# 03_GSM_GPRS_GPS.net
KiCad netlist of a schematic drawn in Altium Designer
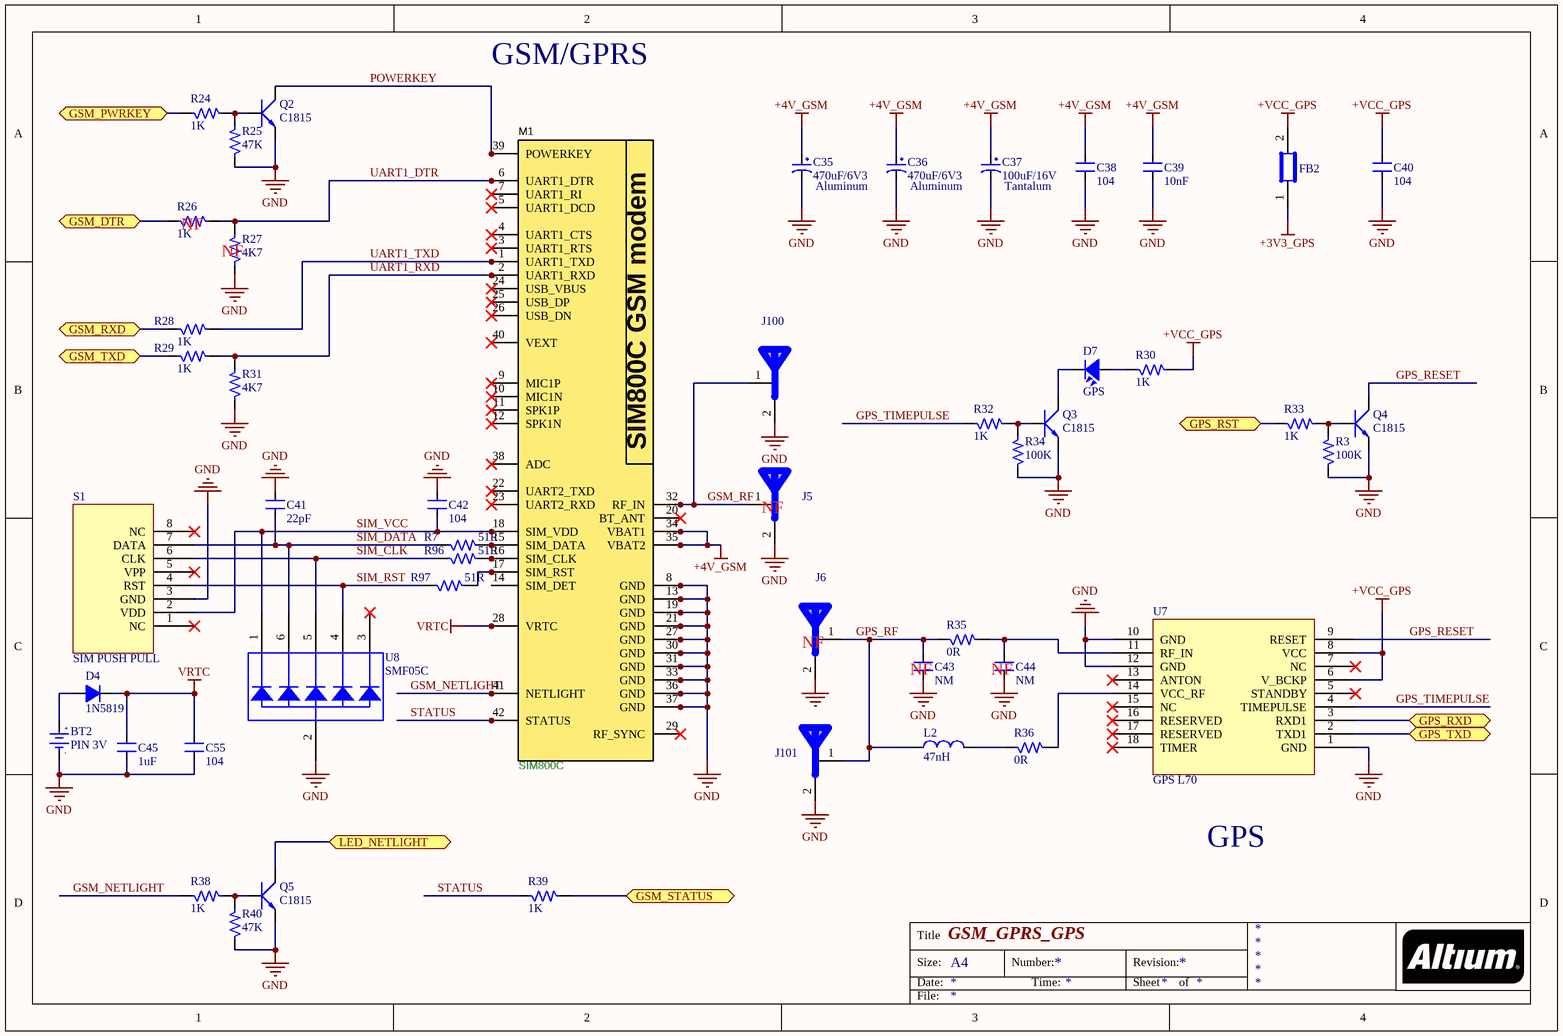
[diagram p0: [03] GSM_GPRS_GPS.SchDoc]

(export (version "E")
  (design (tool "Eeschema 10.0.6"))
  (components
    (comp (ref "BT2")
      (value "PIN 3V")
      (footprint "PIN3V_mini")
      (description "Battery 3VDC")
      (libsource (lib "khapham") (part "PIN 3V"))
    )
    (comp (ref "C35")
      (value "470uF/6V3")
      (footprint "C_Alu_6.3x7.7")
      (description "Cap Aluminum")
      (libsource (lib "khapham") (part "C-Alu-Tantalum"))
    )
    (comp (ref "C36")
      (value "470uF/6V3")
      (footprint "C_Alu_6.3x7.7")
      (description "Cap Aluminum")
      (libsource (lib "khapham") (part "C-Alu-Tantalum"))
    )
    (comp (ref "C37")
      (value "100uF/16V")
      (footprint "C_7343_40")
      (description "Cap Tantalum 7343")
      (libsource (lib "khapham") (part "C-Alu-Tantalum"))
    )
    (comp (ref "C38")
      (value "104")
      (footprint "C0603 SMT")
      (description "Cap SMD")
      (libsource (lib "khapham") (part "CM"))
    )
    (comp (ref "C39")
      (value "10nF")
      (footprint "C0603 SMT")
      (description "Cap SMD")
      (libsource (lib "khapham") (part "CM"))
    )
    (comp (ref "C40")
      (value "104")
      (footprint "C0603 SMT")
      (description "Cap SMD")
      (libsource (lib "khapham") (part "CM"))
    )
    (comp (ref "C41")
      (value "22pF")
      (footprint "C0603 SMT")
      (description "Cap SMD")
      (libsource (lib "khapham") (part "CM"))
    )
    (comp (ref "C42")
      (value "104")
      (footprint "C0603 SMT")
      (description "Cap SMD")
      (libsource (lib "khapham") (part "CM"))
    )
    (comp (ref "C43")
      (value "NM")
      (footprint "C0603 SMT")
      (description "Cap SMD")
      (libsource (lib "khapham") (part "CM"))
    )
    (comp (ref "C44")
      (value "NM")
      (footprint "C0603 SMT")
      (description "Cap SMD")
      (libsource (lib "khapham") (part "CM"))
    )
    (comp (ref "C45")
      (value "1uF")
      (footprint "C0603 SMT")
      (description "Cap SMD")
      (libsource (lib "khapham") (part "CM"))
    )
    (comp (ref "C55")
      (value "104")
      (footprint "C0603 SMT")
      (description "Cap SMD")
      (libsource (lib "khapham") (part "CM"))
    )
    (comp (ref "D4")
      (value "1N5819")
      (footprint "SOD123")
      (description "Diode 1A")
      (libsource (lib "khapham") (part "D1A"))
    )
    (comp (ref "D7")
      (value "GPS")
      (footprint "Led_0603_RED")
      (description "LED Single colour Green and Red")
      (libsource (lib "khapham") (part "LED"))
    )
    (comp (ref "FB2")
      (value "BLM21PG600SN1D")
      (footprint "R0805")
      (description "Ferrite Bead")
      (libsource (lib "khapham") (part "Ferrite Bead"))
    )
    (comp (ref "J5") (value "GSM") (footprint "Antenna-IPEX") (libsource (lib "khapham") (part "ANTEN")))
    (comp (ref "J6") (value "GPS") (footprint "Antenna-IPEX") (libsource (lib "khapham") (part "ANTEN")))
    (comp (ref "J100")
      (value "GPS_ANTENNA")
      (footprint "Antenna-MCX5.08-H5")
      (libsource (lib "khapham") (part "ANTEN"))
    )
    (comp (ref "J101")
      (value "GPS_ANTENNA")
      (footprint "Antenna-MCX5.08-H5")
      (libsource (lib "khapham") (part "ANTEN"))
    )
    (comp (ref "L2")
      (value "47nH")
      (footprint "C0805")
      (description "Inductor")
      (libsource (lib "khapham") (part "L1"))
    )
    (comp (ref "M1") (value "SIM800C") (footprint "SIM800C") (libsource (lib "khapham") (part "SIM800C")))
    (comp (ref "Q2")
      (value "C1815")
      (footprint "SOT23B")
      (description "NPN 600mW, ECB")
      (libsource (lib "khapham") (part "C1815"))
    )
    (comp (ref "Q3")
      (value "C1815")
      (footprint "SOT23B")
      (description "NPN 600mW, ECB")
      (libsource (lib "khapham") (part "C1815"))
    )
    (comp (ref "Q4")
      (value "C1815")
      (footprint "SOT23B")
      (description "NPN 600mW, ECB")
      (libsource (lib "khapham") (part "C1815"))
    )
    (comp (ref "Q5")
      (value "C1815")
      (footprint "SOT23B")
      (description "NPN 600mW, ECB")
      (libsource (lib "khapham") (part "C1815"))
    )
    (comp (ref "R3")
      (value "100K")
      (footprint "R0603 -SMT")
      (description "Resistor SMD")
      (libsource (lib "khapham") (part "RM"))
    )
    (comp (ref "R7")
      (value "51R")
      (footprint "R0603 -SMT")
      (description "Resistor SMD")
      (libsource (lib "khapham") (part "RM"))
    )
    (comp (ref "R24")
      (value "1K")
      (footprint "R0603 -SMT")
      (description "Resistor SMD")
      (libsource (lib "khapham") (part "RM"))
    )
    (comp (ref "R25")
      (value "47K")
      (footprint "R0603 -SMT")
      (description "Resistor SMD")
      (libsource (lib "khapham") (part "RM"))
    )
    (comp (ref "R26")
      (value "1K")
      (footprint "R0603 -SMT")
      (description "Resistor SMD")
      (libsource (lib "khapham") (part "RM"))
    )
    (comp (ref "R27")
      (value "4K7")
      (footprint "R0603 -SMT")
      (description "Resistor SMD")
      (libsource (lib "khapham") (part "RM"))
    )
    (comp (ref "R28")
      (value "1K")
      (footprint "R0603 -SMT")
      (description "Resistor SMD")
      (libsource (lib "khapham") (part "RM"))
    )
    (comp (ref "R29")
      (value "1K")
      (footprint "R0603 -SMT")
      (description "Resistor SMD")
      (libsource (lib "khapham") (part "RM"))
    )
    (comp (ref "R30")
      (value "1K")
      (footprint "R0603 -SMT")
      (description "Resistor SMD")
      (libsource (lib "khapham") (part "RM"))
    )
    (comp (ref "R31")
      (value "4K7")
      (footprint "R0603 -SMT")
      (description "Resistor SMD")
      (libsource (lib "khapham") (part "RM"))
    )
    (comp (ref "R32")
      (value "1K")
      (footprint "R0603 -SMT")
      (description "Resistor SMD")
      (libsource (lib "khapham") (part "RM"))
    )
    (comp (ref "R33")
      (value "1K")
      (footprint "R0603 -SMT")
      (description "Resistor SMD")
      (libsource (lib "khapham") (part "RM"))
    )
    (comp (ref "R34")
      (value "100K")
      (footprint "R0603 -SMT")
      (description "Resistor SMD")
      (libsource (lib "khapham") (part "RM"))
    )
    (comp (ref "R35")
      (value "0R")
      (footprint "R0603 -SMT")
      (description "Resistor SMD")
      (libsource (lib "khapham") (part "RM"))
    )
    (comp (ref "R36")
      (value "0R")
      (footprint "R0603 -SMT")
      (description "Resistor SMD")
      (libsource (lib "khapham") (part "RM"))
    )
    (comp (ref "R38")
      (value "1K")
      (footprint "R0603 -SMT")
      (description "Resistor SMD")
      (libsource (lib "khapham") (part "RM"))
    )
    (comp (ref "R39")
      (value "1K")
      (footprint "R0603 -SMT")
      (description "Resistor SMD")
      (libsource (lib "khapham") (part "RM"))
    )
    (comp (ref "R40")
      (value "47K")
      (footprint "R0603 -SMT")
      (description "Resistor SMD")
      (libsource (lib "khapham") (part "RM"))
    )
    (comp (ref "R96")
      (value "51R")
      (footprint "R0603 -SMT")
      (description "Resistor SMD")
      (libsource (lib "khapham") (part "RM"))
    )
    (comp (ref "R97")
      (value "51R")
      (footprint "R0603 -SMT")
      (description "Resistor SMD")
      (libsource (lib "khapham") (part "RM"))
    )
    (comp (ref "S1")
      (value "SIM PUSH PULL")
      (footprint "Sim Push Push")
      (libsource (lib "khapham") (part "SIM SOCKET PUSH PULL"))
    )
    (comp (ref "U7") (value "GPS L70") (footprint "GPS L70") (libsource (lib "khapham") (part "GPS L70")))
    (comp (ref "U8")
      (value "SMF05C")
      (footprint "SOT_363_6")
      (description "ESD Protection")
      (libsource (lib "khapham") (part "SMF05C"))
    )
  )
  (nets
    (net (code "1") (name "+3V3_GPS") (class "Default")
      (node (ref "FB2") (pin "1") (pinfunction "1_1") (pintype "passive"))
    )
    (net (code "2") (name "+4V_GSM") (class "Default")
      (node (ref "C35") (pin "1") (pinfunction "1_1") (pintype "passive"))
      (node (ref "C36") (pin "1") (pinfunction "1_1") (pintype "passive"))
      (node (ref "C37") (pin "1") (pinfunction "1_1") (pintype "passive"))
      (node (ref "C38") (pin "1") (pinfunction "1_1") (pintype "passive"))
      (node (ref "C39") (pin "1") (pinfunction "1_1") (pintype "passive"))
      (node (ref "M1") (pin "34") (pinfunction "VBAT1_34") (pintype "passive"))
      (node (ref "M1") (pin "35") (pinfunction "VBAT2_35") (pintype "passive"))
    )
    (net (code "3") (name "+VCC_GPS") (class "Default")
      (node (ref "C40") (pin "2") (pinfunction "2_2") (pintype "passive"))
      (node (ref "FB2") (pin "2") (pinfunction "2_2") (pintype "passive"))
      (node (ref "R30") (pin "2") (pinfunction "2_2") (pintype "passive"))
      (node (ref "U7") (pin "6") (pinfunction "V_BCKP_6") (pintype "passive"))
      (node (ref "U7") (pin "8") (pinfunction "VCC_8") (pintype "passive"))
    )
    (net (code "4") (name "/GPS_RESET") (class "Default")
      (node (ref "Q4") (pin "2") (pinfunction "C_2") (pintype "passive"))
      (node (ref "U7") (pin "9") (pinfunction "RESET_9") (pintype "passive"))
    )
    (net (code "5") (name "/GPS_RF") (class "Default")
      (node (ref "C43") (pin "2") (pinfunction "2_2") (pintype "passive"))
      (node (ref "J101") (pin "1") (pinfunction "GND_1") (pintype "passive"))
      (node (ref "J6") (pin "1") (pinfunction "GND_1") (pintype "passive"))
      (node (ref "L2") (pin "1") (pinfunction "1_1") (pintype "passive"))
      (node (ref "R35") (pin "1") (pinfunction "1_1") (pintype "passive"))
    )
    (net (code "6") (name "/GPS_RST") (class "Default")
      (node (ref "R33") (pin "1") (pinfunction "1_1") (pintype "passive"))
    )
    (net (code "7") (name "/GPS_RXD") (class "Default")
      (node (ref "U7") (pin "3") (pinfunction "RXD1_3") (pintype "passive"))
    )
    (net (code "8") (name "/GPS_TIMEPULSE") (class "Default")
      (node (ref "R32") (pin "1") (pinfunction "1_1") (pintype "passive"))
      (node (ref "U7") (pin "4") (pinfunction "TIMEPULSE_4") (pintype "passive"))
    )
    (net (code "9") (name "/GPS_TXD") (class "Default")
      (node (ref "U7") (pin "2") (pinfunction "TXD1_2") (pintype "passive"))
    )
    (net (code "10") (name "/GSM_DTR") (class "Default")
      (node (ref "R26") (pin "1") (pinfunction "1_1") (pintype "passive"))
    )
    (net (code "11") (name "/GSM_NETLIGHT") (class "Default")
      (node (ref "M1") (pin "41") (pinfunction "NETLIGHT_41") (pintype "passive"))
      (node (ref "R38") (pin "1") (pinfunction "1_1") (pintype "passive"))
    )
    (net (code "12") (name "/GSM_PWRKEY") (class "Default")
      (node (ref "R24") (pin "1") (pinfunction "1_1") (pintype "passive"))
    )
    (net (code "13") (name "/GSM_RF") (class "Default")
      (node (ref "J100") (pin "1") (pinfunction "GND_1") (pintype "passive"))
      (node (ref "J5") (pin "1") (pinfunction "GND_1") (pintype "passive"))
      (node (ref "M1") (pin "32") (pinfunction "RF_IN_32") (pintype "passive"))
    )
    (net (code "14") (name "/GSM_RXD") (class "Default")
      (node (ref "R28") (pin "1") (pinfunction "1_1") (pintype "passive"))
    )
    (net (code "15") (name "/GSM_STATUS") (class "Default")
      (node (ref "R39") (pin "2") (pinfunction "2_2") (pintype "passive"))
    )
    (net (code "16") (name "/GSM_TXD") (class "Default")
      (node (ref "R29") (pin "1") (pinfunction "1_1") (pintype "passive"))
    )
    (net (code "17") (name "/LED_NETLIGHT") (class "Default")
      (node (ref "Q5") (pin "2") (pinfunction "C_2") (pintype "passive"))
    )
    (net (code "18") (name "/POWERKEY") (class "Default")
      (node (ref "M1") (pin "39") (pinfunction "POWERKEY_39") (pintype "passive"))
      (node (ref "Q2") (pin "2") (pinfunction "C_2") (pintype "passive"))
    )
    (net (code "19") (name "/SIM_CLK") (class "Default")
      (node (ref "R96") (pin "1") (pinfunction "1_1") (pintype "passive"))
      (node (ref "S1") (pin "6") (pinfunction "CLK_6") (pintype "passive"))
      (node (ref "U8") (pin "5") (pinfunction "K4_5") (pintype "power_in"))
    )
    (net (code "20") (name "/SIM_DATA") (class "Default")
      (node (ref "C41") (pin "1") (pinfunction "1_1") (pintype "passive"))
      (node (ref "R7") (pin "1") (pinfunction "1_1") (pintype "passive"))
      (node (ref "S1") (pin "7") (pinfunction "DATA_7") (pintype "passive"))
      (node (ref "U8") (pin "6") (pinfunction "K5_6") (pintype "passive"))
    )
    (net (code "21") (name "/SIM_RST") (class "Default")
      (node (ref "R97") (pin "1") (pinfunction "1_1") (pintype "passive"))
      (node (ref "S1") (pin "4") (pinfunction "RST_4") (pintype "passive"))
      (node (ref "U8") (pin "4") (pinfunction "K3_4") (pintype "passive"))
    )
    (net (code "22") (name "/SIM_VCC") (class "Default")
      (node (ref "C42") (pin "1") (pinfunction "1_1") (pintype "passive"))
      (node (ref "M1") (pin "18") (pinfunction "SIM_VDD_18") (pintype "passive"))
      (node (ref "S1") (pin "2") (pinfunction "VDD_2") (pintype "passive"))
      (node (ref "U8") (pin "1") (pinfunction "K1_1") (pintype "passive"))
    )
    (net (code "23") (name "/STATUS") (class "Default")
      (node (ref "M1") (pin "42") (pinfunction "STATUS_42") (pintype "passive"))
      (node (ref "R39") (pin "1") (pinfunction "1_1") (pintype "passive"))
    )
    (net (code "24") (name "/UART1_DTR") (class "Default")
      (node (ref "M1") (pin "6") (pinfunction "UART1_DTR_6") (pintype "passive"))
      (node (ref "R26") (pin "2") (pinfunction "2_2") (pintype "passive"))
      (node (ref "R27") (pin "2") (pinfunction "2_2") (pintype "passive"))
    )
    (net (code "25") (name "/UART1_RXD") (class "Default")
      (node (ref "M1") (pin "2") (pinfunction "UART1_RXD_2") (pintype "passive"))
      (node (ref "R29") (pin "2") (pinfunction "2_2") (pintype "passive"))
      (node (ref "R31") (pin "2") (pinfunction "2_2") (pintype "passive"))
    )
    (net (code "26") (name "/UART1_TXD") (class "Default")
      (node (ref "M1") (pin "1") (pinfunction "UART1_TXD_1") (pintype "passive"))
      (node (ref "R28") (pin "2") (pinfunction "2_2") (pintype "passive"))
    )
    (net (code "27") (name "GND") (class "Default")
      (node (ref "BT2") (pin "2") (pinfunction "GND_2") (pintype "passive"))
      (node (ref "C35") (pin "2") (pinfunction "2_2") (pintype "passive"))
      (node (ref "C36") (pin "2") (pinfunction "2_2") (pintype "passive"))
      (node (ref "C37") (pin "2") (pinfunction "2_2") (pintype "passive"))
      (node (ref "C38") (pin "2") (pinfunction "2_2") (pintype "passive"))
      (node (ref "C39") (pin "2") (pinfunction "2_2") (pintype "passive"))
      (node (ref "C40") (pin "1") (pinfunction "1_1") (pintype "passive"))
      (node (ref "C41") (pin "2") (pinfunction "2_2") (pintype "passive"))
      (node (ref "C42") (pin "2") (pinfunction "2_2") (pintype "passive"))
      (node (ref "C43") (pin "1") (pinfunction "1_1") (pintype "passive"))
      (node (ref "C44") (pin "1") (pinfunction "1_1") (pintype "passive"))
      (node (ref "C45") (pin "1") (pinfunction "1_1") (pintype "passive"))
      (node (ref "C55") (pin "1") (pinfunction "1_1") (pintype "passive"))
      (node (ref "J100") (pin "2") (pinfunction "GND_2") (pintype "passive"))
      (node (ref "J101") (pin "2") (pinfunction "GND_2") (pintype "passive"))
      (node (ref "J5") (pin "2") (pinfunction "GND_2") (pintype "passive"))
      (node (ref "J6") (pin "2") (pinfunction "GND_2") (pintype "passive"))
      (node (ref "M1") (pin "13") (pinfunction "GND_13") (pintype "passive"))
      (node (ref "M1") (pin "19") (pinfunction "GND_19") (pintype "passive"))
      (node (ref "M1") (pin "21") (pinfunction "GND_21") (pintype "passive"))
      (node (ref "M1") (pin "27") (pinfunction "GND_27") (pintype "passive"))
      (node (ref "M1") (pin "30") (pinfunction "GND_30") (pintype "passive"))
      (node (ref "M1") (pin "31") (pinfunction "GND_31") (pintype "passive"))
      (node (ref "M1") (pin "33") (pinfunction "GND_33") (pintype "passive"))
      (node (ref "M1") (pin "36") (pinfunction "GND_36") (pintype "passive"))
      (node (ref "M1") (pin "37") (pinfunction "GND_37") (pintype "passive"))
      (node (ref "M1") (pin "8") (pinfunction "GND_8") (pintype "passive"))
      (node (ref "Q2") (pin "1") (pinfunction "E_1") (pintype "passive"))
      (node (ref "Q3") (pin "1") (pinfunction "E_1") (pintype "passive"))
      (node (ref "Q4") (pin "1") (pinfunction "E_1") (pintype "passive"))
      (node (ref "Q5") (pin "1") (pinfunction "E_1") (pintype "passive"))
      (node (ref "R25") (pin "1") (pinfunction "1_1") (pintype "passive"))
      (node (ref "R27") (pin "1") (pinfunction "1_1") (pintype "passive"))
      (node (ref "R3") (pin "1") (pinfunction "1_1") (pintype "passive"))
      (node (ref "R31") (pin "1") (pinfunction "1_1") (pintype "passive"))
      (node (ref "R34") (pin "1") (pinfunction "1_1") (pintype "passive"))
      (node (ref "R40") (pin "1") (pinfunction "1_1") (pintype "passive"))
      (node (ref "S1") (pin "3") (pinfunction "GND_3") (pintype "passive"))
      (node (ref "U7") (pin "1") (pinfunction "GND_1") (pintype "passive"))
      (node (ref "U7") (pin "10") (pinfunction "GND_10") (pintype "passive"))
      (node (ref "U7") (pin "12") (pinfunction "GND_12") (pintype "passive"))
      (node (ref "U8") (pin "2") (pinfunction "A_2") (pintype "power_in"))
    )
    (net (code "28") (name "Net-(BT2-+3V)") (class "Default")
      (node (ref "BT2") (pin "1") (pinfunction "+3V_1") (pintype "passive"))
      (node (ref "D4") (pin "1") (pinfunction "A_1") (pintype "passive"))
    )
    (net (code "29") (name "Net-(D7-Pad1)") (class "Default")
      (node (ref "D7") (pin "1") (pinfunction "1_1") (pintype "passive"))
      (node (ref "R30") (pin "1") (pinfunction "1_1") (pintype "passive"))
    )
    (net (code "30") (name "Net-(L2-Pad2)") (class "Default")
      (node (ref "L2") (pin "2") (pinfunction "2_2") (pintype "passive"))
      (node (ref "R36") (pin "1") (pinfunction "1_1") (pintype "passive"))
    )
    (net (code "31") (name "Net-(M1-SIM_CLK)") (class "Default")
      (node (ref "M1") (pin "16") (pinfunction "SIM_CLK_16") (pintype "passive"))
      (node (ref "R96") (pin "2") (pinfunction "2_2") (pintype "passive"))
    )
    (net (code "32") (name "Net-(M1-SIM_DATA)") (class "Default")
      (node (ref "M1") (pin "15") (pinfunction "SIM_DATA_15") (pintype "passive"))
      (node (ref "R7") (pin "2") (pinfunction "2_2") (pintype "passive"))
    )
    (net (code "33") (name "Net-(M1-SIM_RST)") (class "Default")
      (node (ref "M1") (pin "17") (pinfunction "SIM_RST_17") (pintype "passive"))
      (node (ref "R97") (pin "2") (pinfunction "2_2") (pintype "passive"))
    )
    (net (code "34") (name "Net-(Q2-B)") (class "Default")
      (node (ref "Q2") (pin "3") (pinfunction "B_3") (pintype "passive"))
      (node (ref "R24") (pin "2") (pinfunction "2_2") (pintype "passive"))
      (node (ref "R25") (pin "2") (pinfunction "2_2") (pintype "passive"))
    )
    (net (code "35") (name "Net-(Q3-B)") (class "Default")
      (node (ref "Q3") (pin "3") (pinfunction "B_3") (pintype "passive"))
      (node (ref "R32") (pin "2") (pinfunction "2_2") (pintype "passive"))
      (node (ref "R34") (pin "2") (pinfunction "2_2") (pintype "passive"))
    )
    (net (code "36") (name "Net-(Q3-C)") (class "Default")
      (node (ref "D7") (pin "2") (pinfunction "2_2") (pintype "passive"))
      (node (ref "Q3") (pin "2") (pinfunction "C_2") (pintype "passive"))
    )
    (net (code "37") (name "Net-(Q4-B)") (class "Default")
      (node (ref "Q4") (pin "3") (pinfunction "B_3") (pintype "passive"))
      (node (ref "R3") (pin "2") (pinfunction "2_2") (pintype "passive"))
      (node (ref "R33") (pin "2") (pinfunction "2_2") (pintype "passive"))
    )
    (net (code "38") (name "Net-(Q5-B)") (class "Default")
      (node (ref "Q5") (pin "3") (pinfunction "B_3") (pintype "passive"))
      (node (ref "R38") (pin "2") (pinfunction "2_2") (pintype "passive"))
      (node (ref "R40") (pin "2") (pinfunction "2_2") (pintype "passive"))
    )
    (net (code "39") (name "Net-(U7-RF_IN)") (class "Default")
      (node (ref "C44") (pin "2") (pinfunction "2_2") (pintype "passive"))
      (node (ref "R35") (pin "2") (pinfunction "2_2") (pintype "passive"))
      (node (ref "U7") (pin "11") (pinfunction "RF_IN_11") (pintype "passive"))
    )
    (net (code "40") (name "Net-(U7-VCC_RF)") (class "Default")
      (node (ref "R36") (pin "2") (pinfunction "2_2") (pintype "passive"))
      (node (ref "U7") (pin "14") (pinfunction "VCC_RF_14") (pintype "passive"))
    )
    (net (code "41") (name "VRTC") (class "Default")
      (node (ref "C45") (pin "2") (pinfunction "2_2") (pintype "passive"))
      (node (ref "C55") (pin "2") (pinfunction "2_2") (pintype "passive"))
      (node (ref "D4") (pin "2") (pinfunction "K_2") (pintype "passive"))
      (node (ref "M1") (pin "28") (pinfunction "VRTC_28") (pintype "passive"))
    )
    (net (code "42") (name "unconnected-(M1-ADC-Pad38)") (class "Default")
      (node (ref "M1") (pin "38") (pinfunction "ADC_38") (pintype "passive+no_connect"))
    )
    (net (code "43") (name "unconnected-(M1-BT_ANT-Pad20)") (class "Default")
      (node (ref "M1") (pin "20") (pinfunction "BT_ANT_20") (pintype "passive+no_connect"))
    )
    (net (code "44") (name "unconnected-(M1-MIC1N-Pad10)") (class "Default")
      (node (ref "M1") (pin "10") (pinfunction "MIC1N_10") (pintype "passive+no_connect"))
    )
    (net (code "45") (name "unconnected-(M1-MIC1P-Pad9)") (class "Default")
      (node (ref "M1") (pin "9") (pinfunction "MIC1P_9") (pintype "passive+no_connect"))
    )
    (net (code "46") (name "unconnected-(M1-RF_SYNC-Pad29)") (class "Default")
      (node (ref "M1") (pin "29") (pinfunction "RF_SYNC_29") (pintype "passive+no_connect"))
    )
    (net (code "47") (name "unconnected-(M1-SIM_DET-Pad14)") (class "Default")
      (node (ref "M1") (pin "14") (pinfunction "SIM_DET_14") (pintype "passive"))
    )
    (net (code "48") (name "unconnected-(M1-SPK1N-Pad12)") (class "Default")
      (node (ref "M1") (pin "12") (pinfunction "SPK1N_12") (pintype "passive+no_connect"))
    )
    (net (code "49") (name "unconnected-(M1-SPK1P-Pad11)") (class "Default")
      (node (ref "M1") (pin "11") (pinfunction "SPK1P_11") (pintype "passive+no_connect"))
    )
    (net (code "50") (name "unconnected-(M1-UART1_CTS-Pad4)") (class "Default")
      (node (ref "M1") (pin "4") (pinfunction "UART1_CTS_4") (pintype "passive+no_connect"))
    )
    (net (code "51") (name "unconnected-(M1-UART1_DCD-Pad5)") (class "Default")
      (node (ref "M1") (pin "5") (pinfunction "UART1_DCD_5") (pintype "passive+no_connect"))
    )
    (net (code "52") (name "unconnected-(M1-UART1_RI-Pad7)") (class "Default")
      (node (ref "M1") (pin "7") (pinfunction "UART1_RI_7") (pintype "passive+no_connect"))
    )
    (net (code "53") (name "unconnected-(M1-UART1_RTS-Pad3)") (class "Default")
      (node (ref "M1") (pin "3") (pinfunction "UART1_RTS_3") (pintype "passive+no_connect"))
    )
    (net (code "54") (name "unconnected-(M1-UART2_RXD-Pad23)") (class "Default")
      (node (ref "M1") (pin "23") (pinfunction "UART2_RXD_23") (pintype "passive+no_connect"))
    )
    (net (code "55") (name "unconnected-(M1-UART2_TXD-Pad22)") (class "Default")
      (node (ref "M1") (pin "22") (pinfunction "UART2_TXD_22") (pintype "passive+no_connect"))
    )
    (net (code "56") (name "unconnected-(M1-USB_DN-Pad26)") (class "Default")
      (node (ref "M1") (pin "26") (pinfunction "USB_DN_26") (pintype "passive+no_connect"))
    )
    (net (code "57") (name "unconnected-(M1-USB_DP-Pad25)") (class "Default")
      (node (ref "M1") (pin "25") (pinfunction "USB_DP_25") (pintype "passive+no_connect"))
    )
    (net (code "58") (name "unconnected-(M1-USB_VBUS-Pad24)") (class "Default")
      (node (ref "M1") (pin "24") (pinfunction "USB_VBUS_24") (pintype "passive+no_connect"))
    )
    (net (code "59") (name "unconnected-(M1-VEXT-Pad40)") (class "Default")
      (node (ref "M1") (pin "40") (pinfunction "VEXT_40") (pintype "passive+no_connect"))
    )
    (net (code "60") (name "unconnected-(S1-NC-Pad1)") (class "Default")
      (node (ref "S1") (pin "1") (pinfunction "NC_1") (pintype "passive+no_connect"))
    )
    (net (code "61") (name "unconnected-(S1-NC-Pad8)") (class "Default")
      (node (ref "S1") (pin "8") (pinfunction "NC_8") (pintype "passive+no_connect"))
    )
    (net (code "62") (name "unconnected-(S1-VPP-Pad5)") (class "Default")
      (node (ref "S1") (pin "5") (pinfunction "VPP_5") (pintype "passive+no_connect"))
    )
    (net (code "63") (name "unconnected-(U7-ANTON-Pad13)") (class "Default")
      (node (ref "U7") (pin "13") (pinfunction "ANTON_13") (pintype "passive+no_connect"))
    )
    (net (code "64") (name "unconnected-(U7-NC-Pad7)") (class "Default")
      (node (ref "U7") (pin "7") (pinfunction "NC_7") (pintype "passive+no_connect"))
    )
    (net (code "65") (name "unconnected-(U7-NC-Pad15)") (class "Default")
      (node (ref "U7") (pin "15") (pinfunction "NC_15") (pintype "passive+no_connect"))
    )
    (net (code "66") (name "unconnected-(U7-RESERVED-Pad16)") (class "Default")
      (node (ref "U7") (pin "16") (pinfunction "RESERVED_16") (pintype "passive+no_connect"))
    )
    (net (code "67") (name "unconnected-(U7-RESERVED-Pad17)") (class "Default")
      (node (ref "U7") (pin "17") (pinfunction "RESERVED_17") (pintype "passive+no_connect"))
    )
    (net (code "68") (name "unconnected-(U7-STANDBY-Pad5)") (class "Default")
      (node (ref "U7") (pin "5") (pinfunction "STANDBY_5") (pintype "passive+no_connect"))
    )
    (net (code "69") (name "unconnected-(U7-TIMER-Pad18)") (class "Default")
      (node (ref "U7") (pin "18") (pinfunction "TIMER_18") (pintype "passive+no_connect"))
    )
    (net (code "70") (name "unconnected-(U8-K2-Pad3)") (class "Default")
      (node (ref "U8") (pin "3") (pinfunction "K2_3") (pintype "passive+no_connect"))
    )
  )
)
